# 467444_130_3_1-R0.net
KiCad netlist of a schematic drawn in Altium Designer
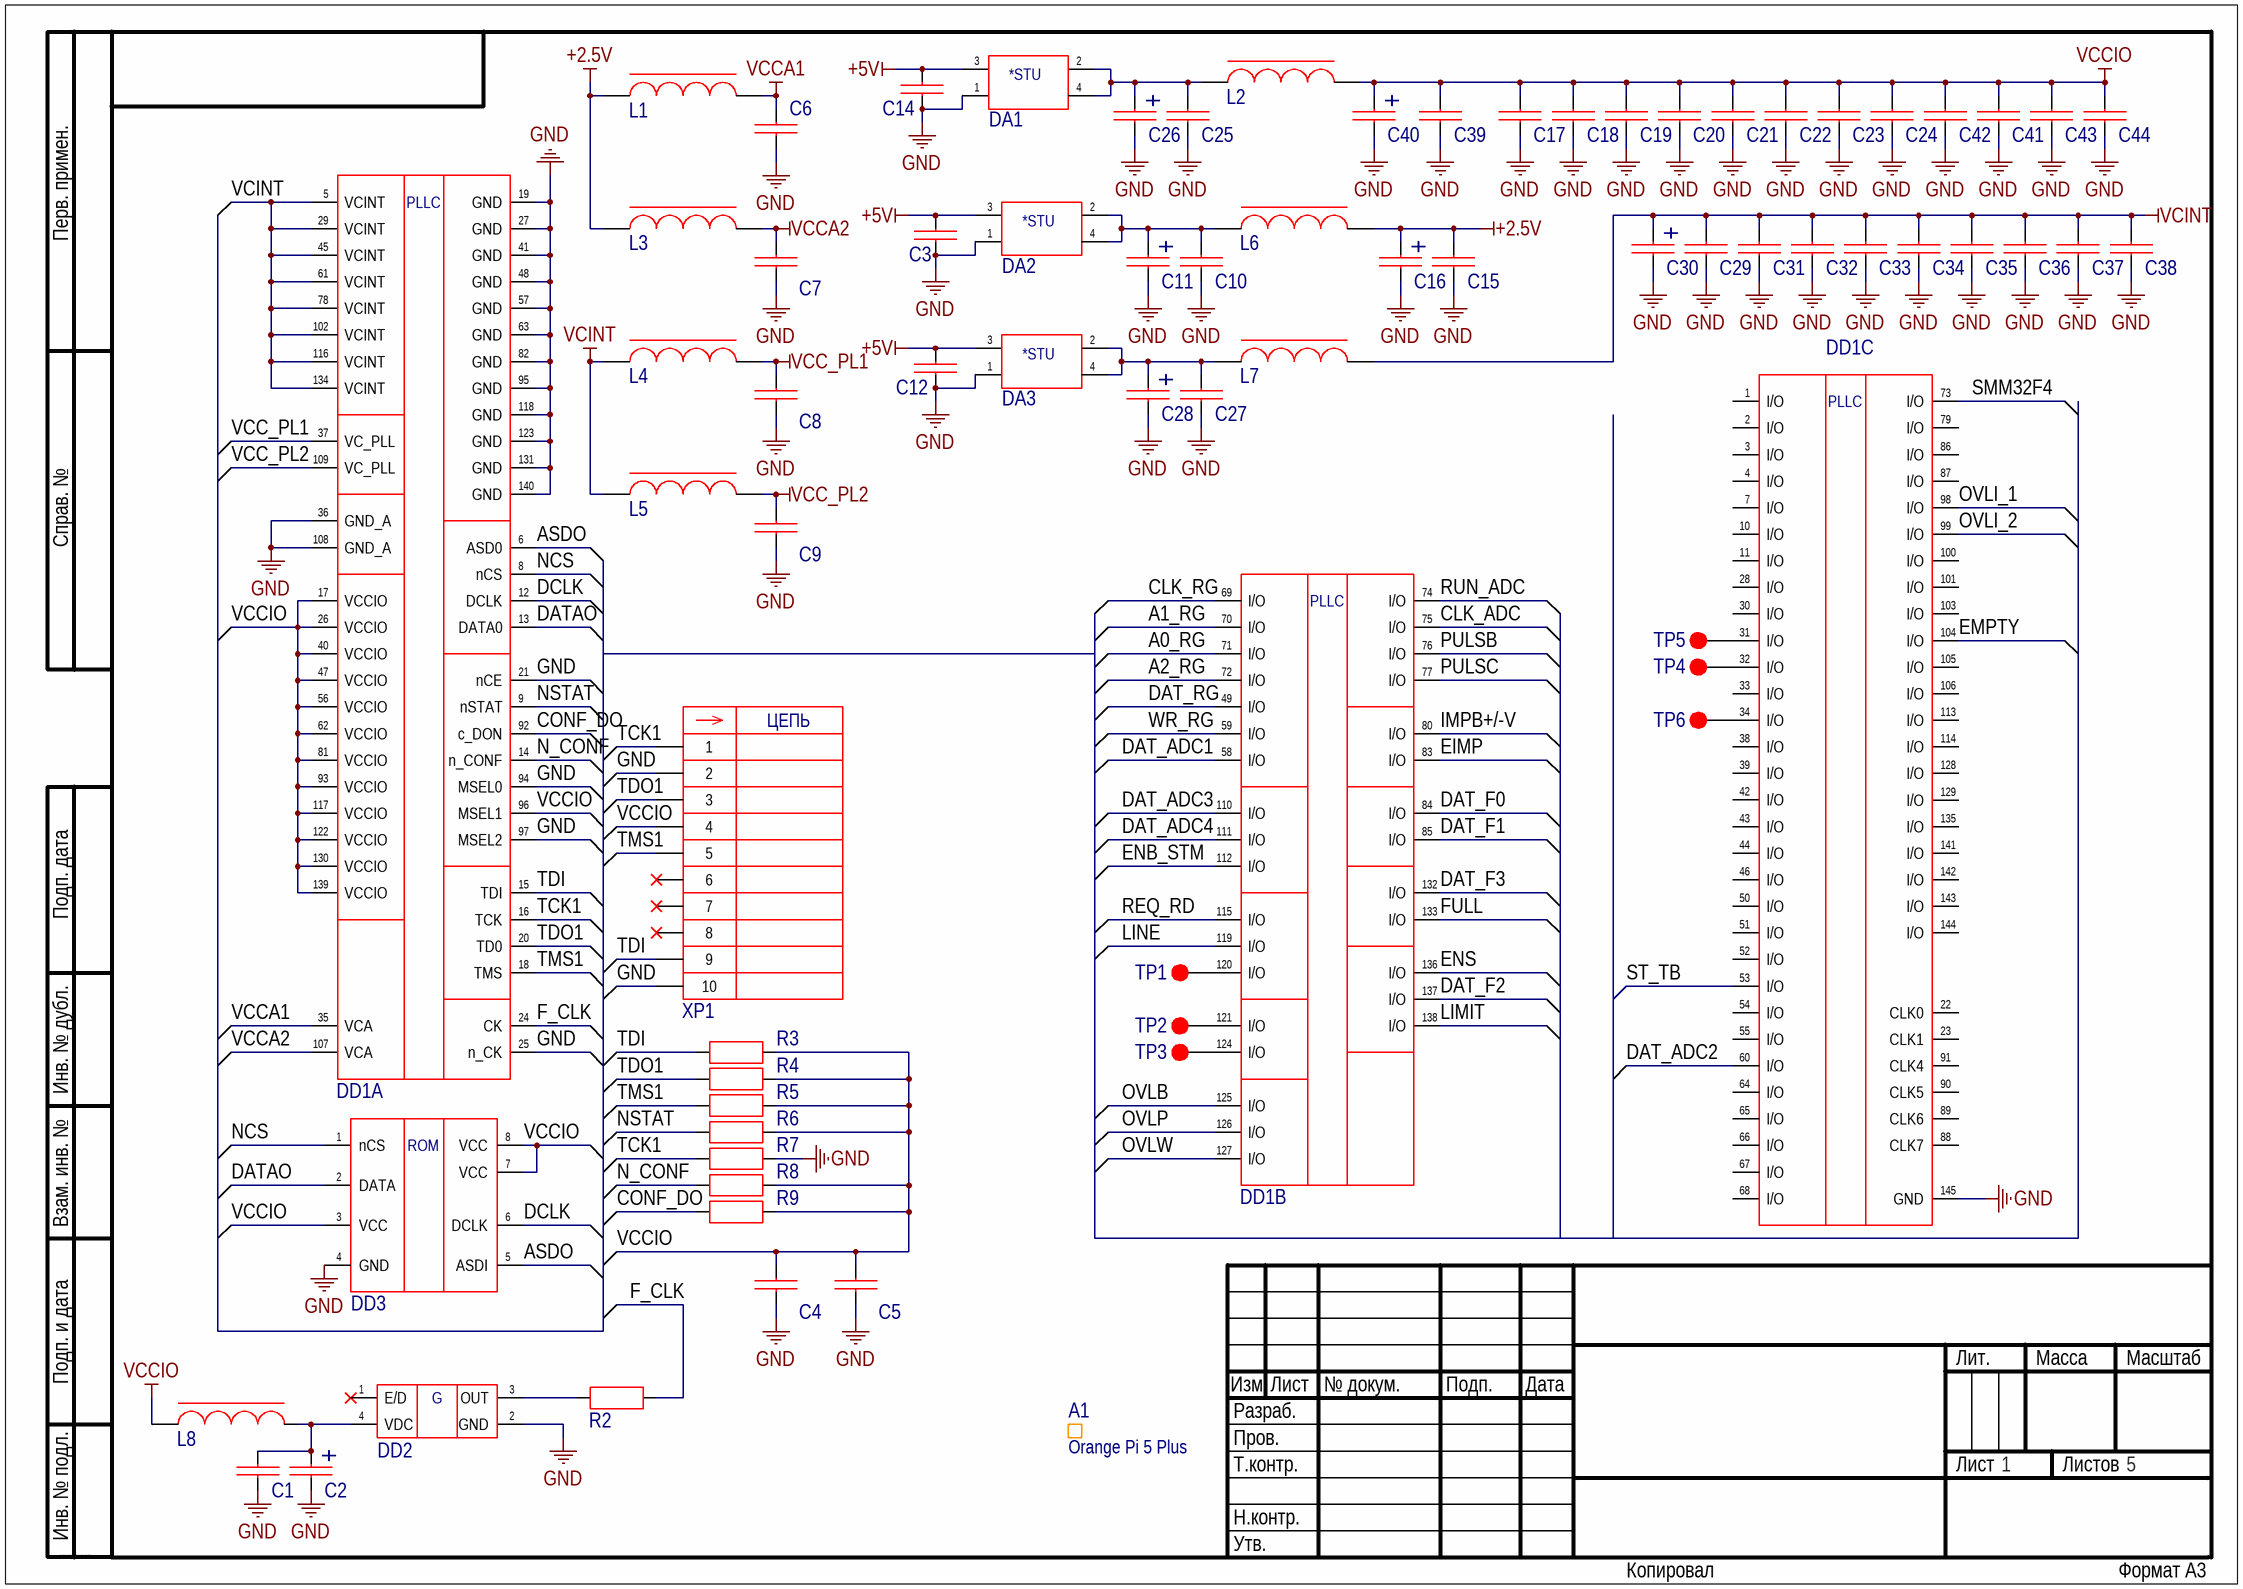
[diagram p0: УШЯИ.467444.130Э3_1-R0.SchDoc]

(export (version "E")
  (design (tool "Eeschema 10.0.6"))
  (components
    (comp (ref "A1")
      (value "Orange Pi 5 Plus")
      (footprint "Orange_Pi_5_Plus")
      (description "8GB Rockchip RK3588, HDMI 2.1, Gigabit LAN port, USB2.0/3.0, microSD card slot, USB Type-C")
      (fields (field (name "MANUFACTURER") "Orange Pi"))
      (libsource (lib "lib") (part "0"))
    )
    (comp (ref "C1")
      (value "0,1 µF")
      (footprint "C_0805 [2012 Metric]")
      (description "Неполярный конденсатор")
      (fields (field (name "MANUFACTURER") "Murata") (field (name "VOLTAGE") "50V"))
      (libsource (lib "lib") (part "C_const"))
    )
    (comp (ref "C2")
      (value "4,7 µF")
      (footprint "C+_1210 [3528-21 Metric]")
      (description "Полярный конденсатор")
      (fields (field (name "MANUFACTURER") "KYOCERA AVX") (field (name "VOLTAGE") "20V\r\n10V"))
      (libsource (lib "lib") (part "C_electrolytic"))
    )
    (comp (ref "C3")
      (value "0,1 µF")
      (footprint "C_0805 [2012 Metric]")
      (description "Неполярный конденсатор")
      (fields (field (name "MANUFACTURER") "Murata") (field (name "VOLTAGE") "25V"))
      (libsource (lib "lib") (part "C_const"))
    )
    (comp (ref "C4")
      (value "1 µF")
      (footprint "C_0805 [2012 Metric]")
      (description "Неполярный конденсатор")
      (fields (field (name "MANUFACTURER") "Murata") (field (name "VOLTAGE") "16V"))
      (libsource (lib "lib") (part "C_const"))
    )
    (comp (ref "C5")
      (value "1 µF")
      (footprint "C_0805 [2012 Metric]")
      (description "Неполярный конденсатор")
      (fields (field (name "MANUFACTURER") "Murata") (field (name "VOLTAGE") "16V"))
      (libsource (lib "lib") (part "C_const"))
    )
    (comp (ref "C6")
      (value "0,1 µF")
      (footprint "C_0805 [2012 Metric]")
      (description "Неполярный конденсатор")
      (fields (field (name "MANUFACTURER") "Murata") (field (name "VOLTAGE") "25V"))
      (libsource (lib "lib") (part "C_const"))
    )
    (comp (ref "C7")
      (value "0,1 µF")
      (footprint "C_0805 [2012 Metric]")
      (description "Неполярный конденсатор")
      (fields (field (name "MANUFACTURER") "Murata") (field (name "VOLTAGE") "25V"))
      (libsource (lib "lib") (part "C_const"))
    )
    (comp (ref "C8")
      (value "0,1 µF")
      (footprint "C_0805 [2012 Metric]")
      (description "Неполярный конденсатор")
      (fields (field (name "MANUFACTURER") "Murata") (field (name "VOLTAGE") "25V"))
      (libsource (lib "lib") (part "C_const"))
    )
    (comp (ref "C9")
      (value "0,1 µF")
      (footprint "C_0805 [2012 Metric]")
      (description "Неполярный конденсатор")
      (fields (field (name "MANUFACTURER") "Murata") (field (name "VOLTAGE") "25V"))
      (libsource (lib "lib") (part "C_const"))
    )
    (comp (ref "C10")
      (value "0,1 µF")
      (footprint "C_0805 [2012 Metric]")
      (description "Неполярный конденсатор")
      (fields (field (name "MANUFACTURER") "Murata") (field (name "VOLTAGE") "25V"))
      (libsource (lib "lib") (part "C_const"))
    )
    (comp (ref "C11")
      (value "4,7 µF")
      (footprint "C+_1210 [3528-21 Metric]")
      (description "Полярный конденсатор")
      (fields (field (name "MANUFACTURER") "KYOCERA AVX") (field (name "VOLTAGE") "20V\r\n10V"))
      (libsource (lib "lib") (part "C_electrolytic"))
    )
    (comp (ref "C12")
      (value "0,1 µF")
      (footprint "C_0805 [2012 Metric]")
      (description "Неполярный конденсатор")
      (fields (field (name "MANUFACTURER") "Murata") (field (name "VOLTAGE") "25V"))
      (libsource (lib "lib") (part "C_const"))
    )
    (comp (ref "C14")
      (value "0,1 µF")
      (footprint "C_0805 [2012 Metric]")
      (description "Неполярный конденсатор")
      (fields (field (name "MANUFACTURER") "Murata") (field (name "VOLTAGE") "25V"))
      (libsource (lib "lib") (part "C_const"))
    )
    (comp (ref "C15")
      (value "0,1 µF")
      (footprint "C_0805 [2012 Metric]")
      (description "Неполярный конденсатор")
      (fields (field (name "MANUFACTURER") "Murata") (field (name "VOLTAGE") "25V"))
      (libsource (lib "lib") (part "C_const"))
    )
    (comp (ref "C16")
      (value "10 µF")
      (footprint "C+_1210 [3528-21 Metric]")
      (description "Полярный конденсатор")
      (fields (field (name "MANUFACTURER") "KYOCERA AVX") (field (name "VOLTAGE") "20V\r\n10V"))
      (libsource (lib "lib") (part "C_electrolytic"))
    )
    (comp (ref "C17")
      (value "0,1 µF")
      (footprint "C_0805 [2012 Metric]")
      (description "Неполярный конденсатор")
      (fields (field (name "MANUFACTURER") "Murata") (field (name "VOLTAGE") "25V"))
      (libsource (lib "lib") (part "C_const"))
    )
    (comp (ref "C18")
      (value "0,1 µF")
      (footprint "C_0805 [2012 Metric]")
      (description "Неполярный конденсатор")
      (fields (field (name "MANUFACTURER") "Murata") (field (name "VOLTAGE") "25V"))
      (libsource (lib "lib") (part "C_const"))
    )
    (comp (ref "C19")
      (value "0,1 µF")
      (footprint "C_0805 [2012 Metric]")
      (description "Неполярный конденсатор")
      (fields (field (name "MANUFACTURER") "Murata") (field (name "VOLTAGE") "25V"))
      (libsource (lib "lib") (part "C_const"))
    )
    (comp (ref "C20")
      (value "0,1 µF")
      (footprint "C_0805 [2012 Metric]")
      (description "Неполярный конденсатор")
      (fields (field (name "MANUFACTURER") "Murata") (field (name "VOLTAGE") "25V"))
      (libsource (lib "lib") (part "C_const"))
    )
    (comp (ref "C21")
      (value "0,1 µF")
      (footprint "C_0805 [2012 Metric]")
      (description "Неполярный конденсатор")
      (fields (field (name "MANUFACTURER") "Murata") (field (name "VOLTAGE") "25V"))
      (libsource (lib "lib") (part "C_const"))
    )
    (comp (ref "C22")
      (value "0,1 µF")
      (footprint "C_0805 [2012 Metric]")
      (description "Неполярный конденсатор")
      (fields (field (name "MANUFACTURER") "Murata") (field (name "VOLTAGE") "25V"))
      (libsource (lib "lib") (part "C_const"))
    )
    (comp (ref "C23")
      (value "0,1 µF")
      (footprint "C_0805 [2012 Metric]")
      (description "Неполярный конденсатор")
      (fields (field (name "MANUFACTURER") "Murata") (field (name "VOLTAGE") "25V"))
      (libsource (lib "lib") (part "C_const"))
    )
    (comp (ref "C24")
      (value "0,1 µF")
      (footprint "C_0805 [2012 Metric]")
      (description "Неполярный конденсатор")
      (fields (field (name "MANUFACTURER") "Murata") (field (name "VOLTAGE") "25V"))
      (libsource (lib "lib") (part "C_const"))
    )
    (comp (ref "C25")
      (value "0,1 µF")
      (footprint "C_0805 [2012 Metric]")
      (description "Неполярный конденсатор")
      (fields (field (name "MANUFACTURER") "Murata") (field (name "VOLTAGE") "25V"))
      (libsource (lib "lib") (part "C_const"))
    )
    (comp (ref "C26")
      (value "4,7 µF")
      (footprint "C+_1210 [3528-21 Metric]")
      (description "Полярный конденсатор")
      (fields (field (name "MANUFACTURER") "KYOCERA AVX") (field (name "VOLTAGE") "20V\r\n10V"))
      (libsource (lib "lib") (part "C_electrolytic"))
    )
    (comp (ref "C27")
      (value "0,1 µF")
      (footprint "C_0805 [2012 Metric]")
      (description "Неполярный конденсатор")
      (fields (field (name "MANUFACTURER") "Murata") (field (name "VOLTAGE") "50V"))
      (libsource (lib "lib") (part "C_const"))
    )
    (comp (ref "C28")
      (value "4,7 µF")
      (footprint "C+_1210 [3528-21 Metric]")
      (description "Полярный конденсатор")
      (fields (field (name "MANUFACTURER") "KYOCERA AVX") (field (name "VOLTAGE") "20V\r\n10V"))
      (libsource (lib "lib") (part "C_electrolytic"))
    )
    (comp (ref "C29")
      (value "0,1 µF")
      (footprint "C_0805 [2012 Metric]")
      (description "Неполярный конденсатор")
      (fields (field (name "MANUFACTURER") "Murata") (field (name "VOLTAGE") "50V"))
      (libsource (lib "lib") (part "C_const"))
    )
    (comp (ref "C30")
      (value "4,7 µF")
      (footprint "C+_1210 [3528-21 Metric]")
      (description "Полярный конденсатор")
      (fields (field (name "MANUFACTURER") "KYOCERA AVX") (field (name "VOLTAGE") "20V\r\n10V"))
      (libsource (lib "lib") (part "C_electrolytic"))
    )
    (comp (ref "C31")
      (value "0,1 µF")
      (footprint "C_0805 [2012 Metric]")
      (description "Неполярный конденсатор")
      (fields (field (name "MANUFACTURER") "Murata") (field (name "VOLTAGE") "50V"))
      (libsource (lib "lib") (part "C_const"))
    )
    (comp (ref "C32")
      (value "0,1 µF")
      (footprint "C_0805 [2012 Metric]")
      (description "Неполярный конденсатор")
      (fields (field (name "MANUFACTURER") "Murata") (field (name "VOLTAGE") "50V"))
      (libsource (lib "lib") (part "C_const"))
    )
    (comp (ref "C33")
      (value "0,1 µF")
      (footprint "C_0805 [2012 Metric]")
      (description "Неполярный конденсатор")
      (fields (field (name "MANUFACTURER") "Murata") (field (name "VOLTAGE") "50V"))
      (libsource (lib "lib") (part "C_const"))
    )
    (comp (ref "C34")
      (value "0,1 µF")
      (footprint "C_0805 [2012 Metric]")
      (description "Неполярный конденсатор")
      (fields (field (name "MANUFACTURER") "Murata") (field (name "VOLTAGE") "50V"))
      (libsource (lib "lib") (part "C_const"))
    )
    (comp (ref "C35")
      (value "0,1 µF")
      (footprint "C_0805 [2012 Metric]")
      (description "Неполярный конденсатор")
      (fields (field (name "MANUFACTURER") "Murata") (field (name "VOLTAGE") "50V"))
      (libsource (lib "lib") (part "C_const"))
    )
    (comp (ref "C36")
      (value "0,1 µF")
      (footprint "C_0805 [2012 Metric]")
      (description "Неполярный конденсатор")
      (fields (field (name "MANUFACTURER") "Murata") (field (name "VOLTAGE") "50V"))
      (libsource (lib "lib") (part "C_const"))
    )
    (comp (ref "C37")
      (value "0,1 µF")
      (footprint "C_0805 [2012 Metric]")
      (description "Неполярный конденсатор")
      (fields (field (name "MANUFACTURER") "Murata") (field (name "VOLTAGE") "50V"))
      (libsource (lib "lib") (part "C_const"))
    )
    (comp (ref "C38")
      (value "0,1 µF")
      (footprint "C_0805 [2012 Metric]")
      (description "Неполярный конденсатор")
      (fields (field (name "MANUFACTURER") "Murata") (field (name "VOLTAGE") "50V"))
      (libsource (lib "lib") (part "C_const"))
    )
    (comp (ref "C39")
      (value "0,1 µF")
      (footprint "C_0805 [2012 Metric]")
      (description "Неполярный конденсатор")
      (fields (field (name "MANUFACTURER") "Murata") (field (name "VOLTAGE") "50V"))
      (libsource (lib "lib") (part "C_const"))
    )
    (comp (ref "C40")
      (value "10 µF")
      (footprint "C+_1210 [3528-21 Metric]")
      (description "Полярный конденсатор")
      (fields (field (name "MANUFACTURER") "KYOCERA AVX") (field (name "VOLTAGE") "20V\r\n10V"))
      (libsource (lib "lib") (part "C_electrolytic"))
    )
    (comp (ref "C41")
      (value "0,1 µF")
      (footprint "C_0805 [2012 Metric]")
      (description "Неполярный конденсатор")
      (fields (field (name "MANUFACTURER") "Murata") (field (name "VOLTAGE") "50V"))
      (libsource (lib "lib") (part "C_const"))
    )
    (comp (ref "C42")
      (value "0,1 µF")
      (footprint "C_0805 [2012 Metric]")
      (description "Неполярный конденсатор")
      (fields (field (name "MANUFACTURER") "Murata") (field (name "VOLTAGE") "50V"))
      (libsource (lib "lib") (part "C_const"))
    )
    (comp (ref "C43")
      (value "0,1 µF")
      (footprint "C_0805 [2012 Metric]")
      (description "Неполярный конденсатор")
      (fields (field (name "MANUFACTURER") "Murata") (field (name "VOLTAGE") "50V"))
      (libsource (lib "lib") (part "C_const"))
    )
    (comp (ref "C44")
      (value "0,1 µF")
      (footprint "C_0805 [2012 Metric]")
      (description "Неполярный конденсатор")
      (fields (field (name "MANUFACTURER") "Murata") (field (name "VOLTAGE") "50V"))
      (libsource (lib "lib") (part "C_const"))
    )
    (comp (ref "DA1")
      (value "LD1117AS33TR")
      (footprint "SOT-223")
      (description "IC, Fixed LDO Voltage Regulator, 5.3V to 10V, 1.15V Dropout, 3.3Vout, 1Aout")
      (fields (field (name "MANUFACTURER") "STMicroelectronics"))
      (libsource (lib "lib") (part "VolReg_LD1117AS33TR"))
    )
    (comp (ref "DA2")
      (value "LD1117AS25TR")
      (footprint "SOT-223")
      (description "IC, Linear Voltage Regulator, 1 Output, 1V Dropout, 2.5Vout, 1Aout")
      (fields (field (name "MANUFACTURER") "STMicroelectronics"))
      (libsource (lib "lib") (part "VolReg_LD1117AS33TR"))
    )
    (comp (ref "DA3")
      (value "LD1117AS12TR")
      (footprint "SOT-223")
      (description "IC, Fixed LDO Voltage Regulator, 1 Output, 1V Dropout, 1.2Vout, 1Aout")
      (fields (field (name "MANUFACTURER") "STMicroelectronics"))
      (libsource (lib "lib") (part "VolReg_LD1117AS33TR"))
    )
    (comp (ref "DD1")
      (value "EP3C5E144I7")
      (footprint "EQFP-144[20x20]_0.5_22x22x1.6")
      (description "IC, Cyclone III, Field Programmable Gate Array (FPGA), 	1.15V to 1.25V, 315 MHz, 94 I/O")
      (fields (field (name "MANUFACTURER") "Intel"))
      (libsource (lib "lib") (part "EP3C5E144I7"))
    )
    (comp (ref "DD2")
      (value "O 20,0-JO32-B-3.3-1-T1-LF")
      (footprint "JO32")
      (description "Crystals, Oscillators, 20 MHz")
      (fields (field (name "MANUFACTURER") "Jauch Quartz GmbH"))
      (libsource (lib "lib") (part "JO32"))
    )
    (comp (ref "DD3")
      (value "EPCS4SI8N")
      (footprint "SOIC-8_1.27_5x4x1.75")
      (description "IC, FPGA Configuration Memory, Flash, 4 Mbit, 40 MHz, JTAG, Serial")
      (fields (field (name "MANUFACTURER") "Intel"))
      (libsource (lib "lib") (part "EPCS4"))
    )
    (comp (ref "L1")
      (value "0,22 μH")
      (footprint "IND_LQH31CN")
      (fields (field (name "MANUFACTURER") "Murata") (field (name "TOLERANCE") "±20%"))
      (libsource (lib "lib") (part "IND_ferromagnetic/ferrite_core"))
    )
    (comp (ref "L2")
      (value "~")
      (footprint "IND_0805 [2012 Metric]")
      (fields (field (name "MANUFACTURER") "Vishay") (field (name "TOLERANCE") "±25%"))
      (libsource (lib "lib") (part "IND_ferromagnetic/ferrite_core"))
    )
    (comp (ref "L3")
      (value "0,22 μH")
      (footprint "IND_LQH31CN")
      (fields (field (name "MANUFACTURER") "Murata") (field (name "TOLERANCE") "±20%"))
      (libsource (lib "lib") (part "IND_ferromagnetic/ferrite_core"))
    )
    (comp (ref "L4")
      (value "0,22 μH")
      (footprint "IND_LQH31CN")
      (fields (field (name "MANUFACTURER") "Murata") (field (name "TOLERANCE") "±20%"))
      (libsource (lib "lib") (part "IND_ferromagnetic/ferrite_core"))
    )
    (comp (ref "L5")
      (value "0,22 μH")
      (footprint "IND_LQH31CN")
      (fields (field (name "MANUFACTURER") "Murata") (field (name "TOLERANCE") "±20%"))
      (libsource (lib "lib") (part "IND_ferromagnetic/ferrite_core"))
    )
    (comp (ref "L6")
      (value "~")
      (footprint "IND_0805 [2012 Metric]")
      (fields (field (name "MANUFACTURER") "Vishay") (field (name "TOLERANCE") "±25%"))
      (libsource (lib "lib") (part "IND_ferromagnetic/ferrite_core"))
    )
    (comp (ref "L7")
      (value "~")
      (footprint "IND_0805 [2012 Metric]")
      (fields (field (name "MANUFACTURER") "Vishay") (field (name "TOLERANCE") "±25%"))
      (libsource (lib "lib") (part "IND_ferromagnetic/ferrite_core"))
    )
    (comp (ref "L8")
      (value "~")
      (footprint "IND_0805 [2012 Metric]")
      (fields (field (name "MANUFACTURER") "Vishay") (field (name "TOLERANCE") "±25%"))
      (libsource (lib "lib") (part "IND_ferromagnetic/ferrite_core"))
    )
    (comp (ref "R2")
      (value "51R")
      (footprint "R_0805 [2012 Metric]")
      (fields (field (name "TOLERANCE") "±5%"))
      (libsource (lib "lib") (part "R_Const"))
    )
    (comp (ref "R3")
      (value "1k")
      (footprint "R_0805 [2012 Metric]")
      (fields (field (name "TOLERANCE") "±5%"))
      (libsource (lib "lib") (part "R_Const"))
    )
    (comp (ref "R4")
      (value "10k")
      (footprint "R_0805 [2012 Metric]")
      (fields (field (name "TOLERANCE") "±5%"))
      (libsource (lib "lib") (part "R_Const"))
    )
    (comp (ref "R5")
      (value "1k")
      (footprint "R_0805 [2012 Metric]")
      (fields (field (name "TOLERANCE") "±5%"))
      (libsource (lib "lib") (part "R_Const"))
    )
    (comp (ref "R6")
      (value "10k")
      (footprint "R_0805 [2012 Metric]")
      (fields (field (name "TOLERANCE") "±5%"))
      (libsource (lib "lib") (part "R_Const"))
    )
    (comp (ref "R7")
      (value "1k")
      (footprint "R_0805 [2012 Metric]")
      (fields (field (name "TOLERANCE") "±5%"))
      (libsource (lib "lib") (part "R_Const"))
    )
    (comp (ref "R8")
      (value "10k")
      (footprint "R_0805 [2012 Metric]")
      (fields (field (name "TOLERANCE") "±5%"))
      (libsource (lib "lib") (part "R_Const"))
    )
    (comp (ref "R9")
      (value "10k")
      (footprint "R_0805 [2012 Metric]")
      (fields (field (name "TOLERANCE") "±5%"))
      (libsource (lib "lib") (part "R_Const"))
    )
    (comp (ref "TP1") (value "~") (footprint "DSP_1.3") (libsource (lib "lib") (part "TP")))
    (comp (ref "TP2") (value "~") (footprint "DSP_1.3") (libsource (lib "lib") (part "TP")))
    (comp (ref "TP3") (value "~") (footprint "DSP_1.3") (libsource (lib "lib") (part "TP")))
    (comp (ref "TP4") (value "~") (footprint "DSP_1.3") (libsource (lib "lib") (part "TP")))
    (comp (ref "TP5") (value "~") (footprint "DSP_1.3") (libsource (lib "lib") (part "TP")))
    (comp (ref "TP6") (value "~") (footprint "DSP_1.3") (libsource (lib "lib") (part "TP")))
    (comp (ref "XP1")
      (value "PLD-10")
      (footprint "PLD-10")
      (description "Male, 10 pins, 2 rows, Vertical")
      (fields (field (name "MANUFACTURER") "Connfly electronic"))
      (libsource (lib "lib") (part "M_10"))
    )
  )
  (nets
    (net (code "1") (name "+2.5V") (class "Default")
      (node (ref "C15") (pin "2") (pinfunction "2_2") (pintype "passive"))
      (node (ref "C16") (pin "+") (pinfunction "+_+") (pintype "passive"))
      (node (ref "L1") (pin "1") (pinfunction "1_1") (pintype "passive"))
      (node (ref "L3") (pin "1") (pinfunction "1_1") (pintype "passive"))
      (node (ref "L6") (pin "2") (pinfunction "2_2") (pintype "passive"))
    )
    (net (code "2") (name "+5V") (class "Default")
      (node (ref "C12") (pin "2") (pinfunction "2_2") (pintype "passive"))
      (node (ref "C14") (pin "2") (pinfunction "2_2") (pintype "passive"))
      (node (ref "C3") (pin "2") (pinfunction "2_2") (pintype "passive"))
      (node (ref "DA1") (pin "3") (pinfunction "VIN_3") (pintype "passive"))
      (node (ref "DA2") (pin "3") (pinfunction "VIN_3") (pintype "passive"))
      (node (ref "DA3") (pin "3") (pinfunction "VIN_3") (pintype "passive"))
    )
    (net (code "3") (name "/A0_RG") (class "Default")
      (node (ref "DD1") (pin "71") (pinfunction "I/O_71") (pintype "passive"))
    )
    (net (code "4") (name "/A1_RG") (class "Default")
      (node (ref "DD1") (pin "70") (pinfunction "I/O_70") (pintype "passive"))
    )
    (net (code "5") (name "/A2_RG") (class "Default")
      (node (ref "DD1") (pin "72") (pinfunction "I/O_72") (pintype "passive"))
    )
    (net (code "6") (name "/ASDO") (class "Default")
      (node (ref "DD1") (pin "6") (pinfunction "ASD0_6") (pintype "passive"))
      (node (ref "DD3") (pin "5") (pinfunction "ASDI_5") (pintype "passive"))
    )
    (net (code "7") (name "/CLK_ADC") (class "Default")
      (node (ref "DD1") (pin "75") (pinfunction "I/O_75") (pintype "passive"))
    )
    (net (code "8") (name "/CLK_RG") (class "Default")
      (node (ref "DD1") (pin "69") (pinfunction "I/O_69") (pintype "passive"))
    )
    (net (code "9") (name "/CONF_DO") (class "Default")
      (node (ref "DD1") (pin "92") (pinfunction "c_DON_92") (pintype "passive"))
      (node (ref "R9") (pin "1") (pinfunction "1_1") (pintype "passive"))
    )
    (net (code "10") (name "/DATAO") (class "Default")
      (node (ref "DD1") (pin "13") (pinfunction "DATA0_13") (pintype "passive"))
      (node (ref "DD3") (pin "2") (pinfunction "DATA_2") (pintype "passive"))
    )
    (net (code "11") (name "/DAT_ADC1") (class "Default")
      (node (ref "DD1") (pin "58") (pinfunction "I/O_58") (pintype "passive"))
    )
    (net (code "12") (name "/DAT_ADC2") (class "Default")
      (node (ref "DD1") (pin "60") (pinfunction "I/O_60") (pintype "passive"))
    )
    (net (code "13") (name "/DAT_ADC3") (class "Default")
      (node (ref "DD1") (pin "110") (pinfunction "I/O_110") (pintype "passive"))
    )
    (net (code "14") (name "/DAT_ADC4") (class "Default")
      (node (ref "DD1") (pin "111") (pinfunction "I/O_111") (pintype "passive"))
    )
    (net (code "15") (name "/DAT_F0") (class "Default")
      (node (ref "DD1") (pin "84") (pinfunction "I/O_84") (pintype "passive"))
    )
    (net (code "16") (name "/DAT_F1") (class "Default")
      (node (ref "DD1") (pin "85") (pinfunction "I/O_85") (pintype "passive"))
    )
    (net (code "17") (name "/DAT_F2") (class "Default")
      (node (ref "DD1") (pin "137") (pinfunction "I/O_137") (pintype "passive"))
    )
    (net (code "18") (name "/DAT_F3") (class "Default")
      (node (ref "DD1") (pin "132") (pinfunction "I/O_132") (pintype "passive"))
    )
    (net (code "19") (name "/DAT_RG") (class "Default")
      (node (ref "DD1") (pin "49") (pinfunction "I/O_49") (pintype "passive"))
    )
    (net (code "20") (name "/DCLK") (class "Default")
      (node (ref "DD1") (pin "12") (pinfunction "DCLK_12") (pintype "passive"))
      (node (ref "DD3") (pin "6") (pinfunction "DCLK_6") (pintype "passive"))
    )
    (net (code "21") (name "/EIMP") (class "Default")
      (node (ref "DD1") (pin "83") (pinfunction "I/O_83") (pintype "passive"))
    )
    (net (code "22") (name "/EMPTY") (class "Default")
      (node (ref "DD1") (pin "104") (pinfunction "I/O_104") (pintype "passive"))
    )
    (net (code "23") (name "/ENB_STM") (class "Default")
      (node (ref "DD1") (pin "112") (pinfunction "I/O_112") (pintype "passive"))
    )
    (net (code "24") (name "/ENS") (class "Default")
      (node (ref "DD1") (pin "136") (pinfunction "I/O_136") (pintype "passive"))
    )
    (net (code "25") (name "/FULL") (class "Default")
      (node (ref "DD1") (pin "133") (pinfunction "I/O_133") (pintype "passive"))
    )
    (net (code "26") (name "/F_CLK") (class "Default")
      (node (ref "DD1") (pin "24") (pinfunction "CK_24") (pintype "passive"))
      (node (ref "R2") (pin "2") (pinfunction "2_2") (pintype "passive"))
    )
    (net (code "27") (name "/IMPB+{slash}-V") (class "Default")
      (node (ref "DD1") (pin "80") (pinfunction "I/O_80") (pintype "passive"))
    )
    (net (code "28") (name "/LIMIT") (class "Default")
      (node (ref "DD1") (pin "138") (pinfunction "I/O_138") (pintype "passive"))
    )
    (net (code "29") (name "/LINE") (class "Default")
      (node (ref "DD1") (pin "119") (pinfunction "I/O_119") (pintype "passive"))
    )
    (net (code "30") (name "/NCS") (class "Default")
      (node (ref "DD1") (pin "8") (pinfunction "nCS_8") (pintype "passive"))
      (node (ref "DD3") (pin "1") (pinfunction "nCS_1") (pintype "passive"))
    )
    (net (code "31") (name "/NSTAT") (class "Default")
      (node (ref "DD1") (pin "9") (pinfunction "nSTAT_9") (pintype "passive"))
      (node (ref "R6") (pin "1") (pinfunction "1_1") (pintype "passive"))
    )
    (net (code "32") (name "/N_CONF") (class "Default")
      (node (ref "DD1") (pin "14") (pinfunction "n_CONF_14") (pintype "passive"))
      (node (ref "R8") (pin "1") (pinfunction "1_1") (pintype "passive"))
    )
    (net (code "33") (name "/OVLB") (class "Default")
      (node (ref "DD1") (pin "125") (pinfunction "I/O_125") (pintype "passive"))
    )
    (net (code "34") (name "/OVLI_1") (class "Default")
      (node (ref "DD1") (pin "98") (pinfunction "I/O_98") (pintype "passive"))
    )
    (net (code "35") (name "/OVLI_2") (class "Default")
      (node (ref "DD1") (pin "99") (pinfunction "I/O_99") (pintype "passive"))
    )
    (net (code "36") (name "/OVLP") (class "Default")
      (node (ref "DD1") (pin "126") (pinfunction "I/O_126") (pintype "passive"))
    )
    (net (code "37") (name "/OVLW") (class "Default")
      (node (ref "DD1") (pin "127") (pinfunction "I/O_127") (pintype "passive"))
    )
    (net (code "38") (name "/PULSB") (class "Default")
      (node (ref "DD1") (pin "76") (pinfunction "I/O_76") (pintype "passive"))
    )
    (net (code "39") (name "/PULSC") (class "Default")
      (node (ref "DD1") (pin "77") (pinfunction "I/O_77") (pintype "passive"))
    )
    (net (code "40") (name "/REQ_RD") (class "Default")
      (node (ref "DD1") (pin "115") (pinfunction "I/O_115") (pintype "passive"))
    )
    (net (code "41") (name "/RUN_ADC") (class "Default")
      (node (ref "DD1") (pin "74") (pinfunction "I/O_74") (pintype "passive"))
    )
    (net (code "42") (name "/SMM32F4") (class "Default")
      (node (ref "DD1") (pin "73") (pinfunction "I/O_73") (pintype "passive"))
    )
    (net (code "43") (name "/ST_TB") (class "Default")
      (node (ref "DD1") (pin "53") (pinfunction "I/O_53") (pintype "passive"))
    )
    (net (code "44") (name "/TCK1") (class "Default")
      (node (ref "DD1") (pin "16") (pinfunction "TCK_16") (pintype "passive"))
      (node (ref "R7") (pin "1") (pinfunction "1_1") (pintype "passive"))
      (node (ref "XP1") (pin "1") (pinfunction "1_1") (pintype "passive"))
    )
    (net (code "45") (name "/TDI") (class "Default")
      (node (ref "DD1") (pin "15") (pinfunction "TDI_15") (pintype "passive"))
      (node (ref "R3") (pin "1") (pinfunction "1_1") (pintype "passive"))
      (node (ref "XP1") (pin "9") (pinfunction "9_9") (pintype "passive"))
    )
    (net (code "46") (name "/TDO1") (class "Default")
      (node (ref "DD1") (pin "20") (pinfunction "TD0_20") (pintype "passive"))
      (node (ref "R4") (pin "1") (pinfunction "1_1") (pintype "passive"))
      (node (ref "XP1") (pin "3") (pinfunction "3_3") (pintype "passive"))
    )
    (net (code "47") (name "/TMS1") (class "Default")
      (node (ref "DD1") (pin "18") (pinfunction "TMS_18") (pintype "passive"))
      (node (ref "R5") (pin "1") (pinfunction "1_1") (pintype "passive"))
      (node (ref "XP1") (pin "5") (pinfunction "5_5") (pintype "passive"))
    )
    (net (code "48") (name "/WR_RG") (class "Default")
      (node (ref "DD1") (pin "59") (pinfunction "I/O_59") (pintype "passive"))
    )
    (net (code "49") (name "GND") (class "Default")
      (node (ref "C1") (pin "1") (pinfunction "1_1") (pintype "passive"))
      (node (ref "C10") (pin "1") (pinfunction "1_1") (pintype "passive"))
      (node (ref "C11") (pin "-") (pinfunction "-_-") (pintype "passive"))
      (node (ref "C12") (pin "1") (pinfunction "1_1") (pintype "passive"))
      (node (ref "C14") (pin "1") (pinfunction "1_1") (pintype "passive"))
      (node (ref "C15") (pin "1") (pinfunction "1_1") (pintype "passive"))
      (node (ref "C16") (pin "-") (pinfunction "-_-") (pintype "passive"))
      (node (ref "C17") (pin "1") (pinfunction "1_1") (pintype "passive"))
      (node (ref "C18") (pin "1") (pinfunction "1_1") (pintype "passive"))
      (node (ref "C19") (pin "1") (pinfunction "1_1") (pintype "passive"))
      (node (ref "C2") (pin "-") (pinfunction "-_-") (pintype "passive"))
      (node (ref "C20") (pin "1") (pinfunction "1_1") (pintype "passive"))
      (node (ref "C21") (pin "1") (pinfunction "1_1") (pintype "passive"))
      (node (ref "C22") (pin "1") (pinfunction "1_1") (pintype "passive"))
      (node (ref "C23") (pin "1") (pinfunction "1_1") (pintype "passive"))
      (node (ref "C24") (pin "1") (pinfunction "1_1") (pintype "passive"))
      (node (ref "C25") (pin "1") (pinfunction "1_1") (pintype "passive"))
      (node (ref "C26") (pin "-") (pinfunction "-_-") (pintype "passive"))
      (node (ref "C27") (pin "1") (pinfunction "1_1") (pintype "passive"))
      (node (ref "C28") (pin "-") (pinfunction "-_-") (pintype "passive"))
      (node (ref "C29") (pin "1") (pinfunction "1_1") (pintype "passive"))
      (node (ref "C3") (pin "1") (pinfunction "1_1") (pintype "passive"))
      (node (ref "C30") (pin "-") (pinfunction "-_-") (pintype "passive"))
      (node (ref "C31") (pin "1") (pinfunction "1_1") (pintype "passive"))
      (node (ref "C32") (pin "1") (pinfunction "1_1") (pintype "passive"))
      (node (ref "C33") (pin "1") (pinfunction "1_1") (pintype "passive"))
      (node (ref "C34") (pin "1") (pinfunction "1_1") (pintype "passive"))
      (node (ref "C35") (pin "1") (pinfunction "1_1") (pintype "passive"))
      (node (ref "C36") (pin "1") (pinfunction "1_1") (pintype "passive"))
      (node (ref "C37") (pin "1") (pinfunction "1_1") (pintype "passive"))
      (node (ref "C38") (pin "1") (pinfunction "1_1") (pintype "passive"))
      (node (ref "C39") (pin "1") (pinfunction "1_1") (pintype "passive"))
      (node (ref "C4") (pin "1") (pinfunction "1_1") (pintype "passive"))
      (node (ref "C40") (pin "-") (pinfunction "-_-") (pintype "passive"))
      (node (ref "C41") (pin "1") (pinfunction "1_1") (pintype "passive"))
      (node (ref "C42") (pin "1") (pinfunction "1_1") (pintype "passive"))
      (node (ref "C43") (pin "1") (pinfunction "1_1") (pintype "passive"))
      (node (ref "C44") (pin "1") (pinfunction "1_1") (pintype "passive"))
      (node (ref "C5") (pin "1") (pinfunction "1_1") (pintype "passive"))
      (node (ref "C6") (pin "1") (pinfunction "1_1") (pintype "passive"))
      (node (ref "C7") (pin "1") (pinfunction "1_1") (pintype "passive"))
      (node (ref "C8") (pin "1") (pinfunction "1_1") (pintype "passive"))
      (node (ref "C9") (pin "1") (pinfunction "1_1") (pintype "passive"))
      (node (ref "DA1") (pin "1") (pinfunction "ADJ/GND_1") (pintype "passive"))
      (node (ref "DA2") (pin "1") (pinfunction "ADJ/GND_1") (pintype "passive"))
      (node (ref "DA3") (pin "1") (pinfunction "ADJ/GND_1") (pintype "passive"))
      (node (ref "DD1") (pin "108") (pinfunction "GND_A_108") (pintype "passive"))
      (node (ref "DD1") (pin "118") (pinfunction "GND_118") (pintype "passive"))
      (node (ref "DD1") (pin "123") (pinfunction "GND_123") (pintype "passive"))
      (node (ref "DD1") (pin "131") (pinfunction "GND_131") (pintype "passive"))
      (node (ref "DD1") (pin "140") (pinfunction "GND_140") (pintype "passive"))
      (node (ref "DD1") (pin "145") (pinfunction "GND_145") (pintype "passive"))
      (node (ref "DD1") (pin "19") (pinfunction "GND_19") (pintype "passive"))
      (node (ref "DD1") (pin "21") (pinfunction "nCE_21") (pintype "passive"))
      (node (ref "DD1") (pin "25") (pinfunction "n_CK_25") (pintype "passive"))
      (node (ref "DD1") (pin "27") (pinfunction "GND_27") (pintype "passive"))
      (node (ref "DD1") (pin "36") (pinfunction "GND_A_36") (pintype "passive"))
      (node (ref "DD1") (pin "41") (pinfunction "GND_41") (pintype "passive"))
      (node (ref "DD1") (pin "48") (pinfunction "GND_48") (pintype "passive"))
      (node (ref "DD1") (pin "57") (pinfunction "GND_57") (pintype "passive"))
      (node (ref "DD1") (pin "63") (pinfunction "GND_63") (pintype "passive"))
      (node (ref "DD1") (pin "82") (pinfunction "GND_82") (pintype "passive"))
      (node (ref "DD1") (pin "94") (pinfunction "MSEL0_94") (pintype "passive"))
      (node (ref "DD1") (pin "95") (pinfunction "GND_95") (pintype "passive"))
      (node (ref "DD1") (pin "97") (pinfunction "MSEL2_97") (pintype "passive"))
      (node (ref "DD2") (pin "2") (pinfunction "GND_2") (pintype "passive"))
      (node (ref "DD3") (pin "4") (pinfunction "GND_4") (pintype "passive"))
      (node (ref "R7") (pin "2") (pinfunction "2_2") (pintype "passive"))
      (node (ref "XP1") (pin "10") (pinfunction "10_10") (pintype "passive"))
      (node (ref "XP1") (pin "2") (pinfunction "2_2") (pintype "passive"))
    )
    (net (code "50") (name "Net-(C10-Pad2)") (class "Default")
      (node (ref "C10") (pin "2") (pinfunction "2_2") (pintype "passive"))
      (node (ref "C11") (pin "+") (pinfunction "+_+") (pintype "passive"))
      (node (ref "DA2") (pin "2") (pinfunction "VOUT_2") (pintype "passive"))
      (node (ref "DA2") (pin "4") (pinfunction "VOUT_4") (pintype "passive"))
      (node (ref "L6") (pin "1") (pinfunction "1_1") (pintype "passive"))
    )
    (net (code "51") (name "Net-(C25-Pad2)") (class "Default")
      (node (ref "C25") (pin "2") (pinfunction "2_2") (pintype "passive"))
      (node (ref "C26") (pin "+") (pinfunction "+_+") (pintype "passive"))
      (node (ref "DA1") (pin "2") (pinfunction "VOUT_2") (pintype "passive"))
      (node (ref "DA1") (pin "4") (pinfunction "VOUT_4") (pintype "passive"))
      (node (ref "L2") (pin "1") (pinfunction "1_1") (pintype "passive"))
    )
    (net (code "52") (name "Net-(C27-Pad2)") (class "Default")
      (node (ref "C27") (pin "2") (pinfunction "2_2") (pintype "passive"))
      (node (ref "C28") (pin "+") (pinfunction "+_+") (pintype "passive"))
      (node (ref "DA3") (pin "2") (pinfunction "VOUT_2") (pintype "passive"))
      (node (ref "DA3") (pin "4") (pinfunction "VOUT_4") (pintype "passive"))
      (node (ref "L7") (pin "1") (pinfunction "1_1") (pintype "passive"))
    )
    (net (code "53") (name "Net-(DD1B-I{slash}O-Pad120)") (class "Default")
      (node (ref "DD1") (pin "120") (pinfunction "I/O_120") (pintype "passive"))
      (node (ref "TP1") (pin "1") (pinfunction "1_1") (pintype "passive"))
    )
    (net (code "54") (name "Net-(DD1B-I{slash}O-Pad121)") (class "Default")
      (node (ref "DD1") (pin "121") (pinfunction "I/O_121") (pintype "passive"))
      (node (ref "TP2") (pin "1") (pinfunction "1_1") (pintype "passive"))
    )
    (net (code "55") (name "Net-(DD1B-I{slash}O-Pad124)") (class "Default")
      (node (ref "DD1") (pin "124") (pinfunction "I/O_124") (pintype "passive"))
      (node (ref "TP3") (pin "1") (pinfunction "1_1") (pintype "passive"))
    )
    (net (code "56") (name "Net-(DD1C-I{slash}O-Pad31)") (class "Default")
      (node (ref "DD1") (pin "31") (pinfunction "I/O_31") (pintype "passive"))
      (node (ref "TP5") (pin "1") (pinfunction "1_1") (pintype "passive"))
    )
    (net (code "57") (name "Net-(DD1C-I{slash}O-Pad32)") (class "Default")
      (node (ref "DD1") (pin "32") (pinfunction "I/O_32") (pintype "passive"))
      (node (ref "TP4") (pin "1") (pinfunction "1_1") (pintype "passive"))
    )
    (net (code "58") (name "Net-(DD1C-I{slash}O-Pad34)") (class "Default")
      (node (ref "DD1") (pin "34") (pinfunction "I/O_34") (pintype "passive"))
      (node (ref "TP6") (pin "1") (pinfunction "1_1") (pintype "passive"))
    )
    (net (code "59") (name "Net-(DD2-OUT)") (class "Default")
      (node (ref "DD2") (pin "3") (pinfunction "OUT_3") (pintype "passive"))
      (node (ref "R2") (pin "1") (pinfunction "1_1") (pintype "passive"))
    )
    (net (code "60") (name "Net-(DD2-VDC)") (class "Default")
      (node (ref "C1") (pin "2") (pinfunction "2_2") (pintype "passive"))
      (node (ref "C2") (pin "+") (pinfunction "+_+") (pintype "passive"))
      (node (ref "DD2") (pin "4") (pinfunction "VDC_4") (pintype "passive"))
      (node (ref "L8") (pin "2") (pinfunction "2_2") (pintype "passive"))
    )
    (net (code "61") (name "VCCA1") (class "Default")
      (node (ref "C6") (pin "2") (pinfunction "2_2") (pintype "passive"))
      (node (ref "DD1") (pin "35") (pinfunction "VCA_35") (pintype "passive"))
      (node (ref "L1") (pin "2") (pinfunction "2_2") (pintype "passive"))
    )
    (net (code "62") (name "VCCA2") (class "Default")
      (node (ref "C7") (pin "2") (pinfunction "2_2") (pintype "passive"))
      (node (ref "DD1") (pin "107") (pinfunction "VCA_107") (pintype "passive"))
      (node (ref "L3") (pin "2") (pinfunction "2_2") (pintype "passive"))
    )
    (net (code "63") (name "VCCIO") (class "Default")
      (node (ref "C17") (pin "2") (pinfunction "2_2") (pintype "passive"))
      (node (ref "C18") (pin "2") (pinfunction "2_2") (pintype "passive"))
      (node (ref "C19") (pin "2") (pinfunction "2_2") (pintype "passive"))
      (node (ref "C20") (pin "2") (pinfunction "2_2") (pintype "passive"))
      (node (ref "C21") (pin "2") (pinfunction "2_2") (pintype "passive"))
      (node (ref "C22") (pin "2") (pinfunction "2_2") (pintype "passive"))
      (node (ref "C23") (pin "2") (pinfunction "2_2") (pintype "passive"))
      (node (ref "C24") (pin "2") (pinfunction "2_2") (pintype "passive"))
      (node (ref "C39") (pin "2") (pinfunction "2_2") (pintype "passive"))
      (node (ref "C4") (pin "2") (pinfunction "2_2") (pintype "passive"))
      (node (ref "C40") (pin "+") (pinfunction "+_+") (pintype "passive"))
      (node (ref "C41") (pin "2") (pinfunction "2_2") (pintype "passive"))
      (node (ref "C42") (pin "2") (pinfunction "2_2") (pintype "passive"))
      (node (ref "C43") (pin "2") (pinfunction "2_2") (pintype "passive"))
      (node (ref "C44") (pin "2") (pinfunction "2_2") (pintype "passive"))
      (node (ref "C5") (pin "2") (pinfunction "2_2") (pintype "passive"))
      (node (ref "DD1") (pin "117") (pinfunction "VCCIO_117") (pintype "passive"))
      (node (ref "DD1") (pin "122") (pinfunction "VCCIO_122") (pintype "passive"))
      (node (ref "DD1") (pin "130") (pinfunction "VCCIO_130") (pintype "passive"))
      (node (ref "DD1") (pin "139") (pinfunction "VCCIO_139") (pintype "passive"))
      (node (ref "DD1") (pin "17") (pinfunction "VCCIO_17") (pintype "passive"))
      (node (ref "DD1") (pin "26") (pinfunction "VCCIO_26") (pintype "passive"))
      (node (ref "DD1") (pin "40") (pinfunction "VCCIO_40") (pintype "passive"))
      (node (ref "DD1") (pin "47") (pinfunction "VCCIO_47") (pintype "passive"))
      (node (ref "DD1") (pin "56") (pinfunction "VCCIO_56") (pintype "passive"))
      (node (ref "DD1") (pin "62") (pinfunction "VCCIO_62") (pintype "passive"))
      (node (ref "DD1") (pin "81") (pinfunction "VCCIO_81") (pintype "passive"))
      (node (ref "DD1") (pin "93") (pinfunction "VCCIO_93") (pintype "passive"))
      (node (ref "DD1") (pin "96") (pinfunction "MSEL1_96") (pintype "passive"))
      (node (ref "DD3") (pin "3") (pinfunction "VCC_3") (pintype "passive"))
      (node (ref "DD3") (pin "7") (pinfunction "VCC_7") (pintype "passive"))
      (node (ref "DD3") (pin "8") (pinfunction "VCC_8") (pintype "passive"))
      (node (ref "L2") (pin "2") (pinfunction "2_2") (pintype "passive"))
      (node (ref "L8") (pin "1") (pinfunction "1_1") (pintype "passive"))
      (node (ref "R3") (pin "2") (pinfunction "2_2") (pintype "passive"))
      (node (ref "R4") (pin "2") (pinfunction "2_2") (pintype "passive"))
      (node (ref "R5") (pin "2") (pinfunction "2_2") (pintype "passive"))
      (node (ref "R6") (pin "2") (pinfunction "2_2") (pintype "passive"))
      (node (ref "R8") (pin "2") (pinfunction "2_2") (pintype "passive"))
      (node (ref "R9") (pin "2") (pinfunction "2_2") (pintype "passive"))
      (node (ref "XP1") (pin "4") (pinfunction "4_4") (pintype "passive"))
    )
    (net (code "64") (name "VCC_PL1") (class "Default")
      (node (ref "C8") (pin "2") (pinfunction "2_2") (pintype "passive"))
      (node (ref "DD1") (pin "37") (pinfunction "VC_PLL_37") (pintype "passive"))
      (node (ref "L4") (pin "2") (pinfunction "2_2") (pintype "passive"))
    )
    (net (code "65") (name "VCC_PL2") (class "Default")
      (node (ref "C9") (pin "2") (pinfunction "2_2") (pintype "passive"))
      (node (ref "DD1") (pin "109") (pinfunction "VC_PLL_109") (pintype "passive"))
      (node (ref "L5") (pin "2") (pinfunction "2_2") (pintype "passive"))
    )
    (net (code "66") (name "VCINT") (class "Default")
      (node (ref "C29") (pin "2") (pinfunction "2_2") (pintype "passive"))
      (node (ref "C30") (pin "+") (pinfunction "+_+") (pintype "passive"))
      (node (ref "C31") (pin "2") (pinfunction "2_2") (pintype "passive"))
      (node (ref "C32") (pin "2") (pinfunction "2_2") (pintype "passive"))
      (node (ref "C33") (pin "2") (pinfunction "2_2") (pintype "passive"))
      (node (ref "C34") (pin "2") (pinfunction "2_2") (pintype "passive"))
      (node (ref "C35") (pin "2") (pinfunction "2_2") (pintype "passive"))
      (node (ref "C36") (pin "2") (pinfunction "2_2") (pintype "passive"))
      (node (ref "C37") (pin "2") (pinfunction "2_2") (pintype "passive"))
      (node (ref "C38") (pin "2") (pinfunction "2_2") (pintype "passive"))
      (node (ref "DD1") (pin "102") (pinfunction "VCINT_102") (pintype "passive"))
      (node (ref "DD1") (pin "116") (pinfunction "VCINT_116") (pintype "passive"))
      (node (ref "DD1") (pin "134") (pinfunction "VCINT_134") (pintype "passive"))
      (node (ref "DD1") (pin "29") (pinfunction "VCINT_29") (pintype "passive"))
      (node (ref "DD1") (pin "45") (pinfunction "VCINT_45") (pintype "passive"))
      (node (ref "DD1") (pin "5") (pinfunction "VCINT_5") (pintype "passive"))
      (node (ref "DD1") (pin "61") (pinfunction "VCINT_61") (pintype "passive"))
      (node (ref "DD1") (pin "78") (pinfunction "VCINT_78") (pintype "passive"))
      (node (ref "L4") (pin "1") (pinfunction "1_1") (pintype "passive"))
      (node (ref "L5") (pin "1") (pinfunction "1_1") (pintype "passive"))
      (node (ref "L7") (pin "2") (pinfunction "2_2") (pintype "passive"))
    )
    (net (code "67") (name "unconnected-(DD1C-CLK0-Pad22)") (class "Default")
      (node (ref "DD1") (pin "22") (pinfunction "CLK0_22") (pintype "passive"))
    )
    (net (code "68") (name "unconnected-(DD1C-CLK1-Pad23)") (class "Default")
      (node (ref "DD1") (pin "23") (pinfunction "CLK1_23") (pintype "passive"))
    )
    (net (code "69") (name "unconnected-(DD1C-CLK4-Pad91)") (class "Default")
      (node (ref "DD1") (pin "91") (pinfunction "CLK4_91") (pintype "passive"))
    )
    (net (code "70") (name "unconnected-(DD1C-CLK5-Pad90)") (class "Default")
      (node (ref "DD1") (pin "90") (pinfunction "CLK5_90") (pintype "passive"))
    )
    (net (code "71") (name "unconnected-(DD1C-CLK6-Pad89)") (class "Default")
      (node (ref "DD1") (pin "89") (pinfunction "CLK6_89") (pintype "passive"))
    )
    (net (code "72") (name "unconnected-(DD1C-CLK7-Pad88)") (class "Default")
      (node (ref "DD1") (pin "88") (pinfunction "CLK7_88") (pintype "passive"))
    )
    (net (code "73") (name "unconnected-(DD1C-I{slash}O-Pad1)") (class "Default")
      (node (ref "DD1") (pin "1") (pinfunction "I/O_1") (pintype "passive"))
    )
    (net (code "74") (name "unconnected-(DD1C-I{slash}O-Pad2)") (class "Default")
      (node (ref "DD1") (pin "2") (pinfunction "I/O_2") (pintype "passive"))
    )
    (net (code "75") (name "unconnected-(DD1C-I{slash}O-Pad3)") (class "Default")
      (node (ref "DD1") (pin "3") (pinfunction "I/O_3") (pintype "passive"))
    )
    (net (code "76") (name "unconnected-(DD1C-I{slash}O-Pad4)") (class "Default")
      (node (ref "DD1") (pin "4") (pinfunction "I/O_4") (pintype "passive"))
    )
    (net (code "77") (name "unconnected-(DD1C-I{slash}O-Pad7)") (class "Default")
      (node (ref "DD1") (pin "7") (pinfunction "I/O_7") (pintype "passive"))
    )
    (net (code "78") (name "unconnected-(DD1C-I{slash}O-Pad10)") (class "Default")
      (node (ref "DD1") (pin "10") (pinfunction "I/O_10") (pintype "passive"))
    )
    (net (code "79") (name "unconnected-(DD1C-I{slash}O-Pad11)") (class "Default")
      (node (ref "DD1") (pin "11") (pinfunction "I/O_11") (pintype "passive"))
    )
    (net (code "80") (name "unconnected-(DD1C-I{slash}O-Pad28)") (class "Default")
      (node (ref "DD1") (pin "28") (pinfunction "I/O_28") (pintype "passive"))
    )
    (net (code "81") (name "unconnected-(DD1C-I{slash}O-Pad30)") (class "Default")
      (node (ref "DD1") (pin "30") (pinfunction "I/O_30") (pintype "passive"))
    )
    (net (code "82") (name "unconnected-(DD1C-I{slash}O-Pad33)") (class "Default")
      (node (ref "DD1") (pin "33") (pinfunction "I/O_33") (pintype "passive"))
    )
    (net (code "83") (name "unconnected-(DD1C-I{slash}O-Pad38)") (class "Default")
      (node (ref "DD1") (pin "38") (pinfunction "I/O_38") (pintype "passive"))
    )
    (net (code "84") (name "unconnected-(DD1C-I{slash}O-Pad39)") (class "Default")
      (node (ref "DD1") (pin "39") (pinfunction "I/O_39") (pintype "passive"))
    )
    (net (code "85") (name "unconnected-(DD1C-I{slash}O-Pad42)") (class "Default")
      (node (ref "DD1") (pin "42") (pinfunction "I/O_42") (pintype "passive"))
    )
    (net (code "86") (name "unconnected-(DD1C-I{slash}O-Pad43)") (class "Default")
      (node (ref "DD1") (pin "43") (pinfunction "I/O_43") (pintype "passive"))
    )
    (net (code "87") (name "unconnected-(DD1C-I{slash}O-Pad44)") (class "Default")
      (node (ref "DD1") (pin "44") (pinfunction "I/O_44") (pintype "passive"))
    )
    (net (code "88") (name "unconnected-(DD1C-I{slash}O-Pad46)") (class "Default")
      (node (ref "DD1") (pin "46") (pinfunction "I/O_46") (pintype "passive"))
    )
    (net (code "89") (name "unconnected-(DD1C-I{slash}O-Pad50)") (class "Default")
      (node (ref "DD1") (pin "50") (pinfunction "I/O_50") (pintype "passive"))
    )
    (net (code "90") (name "unconnected-(DD1C-I{slash}O-Pad51)") (class "Default")
      (node (ref "DD1") (pin "51") (pinfunction "I/O_51") (pintype "passive"))
    )
    (net (code "91") (name "unconnected-(DD1C-I{slash}O-Pad52)") (class "Default")
      (node (ref "DD1") (pin "52") (pinfunction "I/O_52") (pintype "passive"))
    )
    (net (code "92") (name "unconnected-(DD1C-I{slash}O-Pad54)") (class "Default")
      (node (ref "DD1") (pin "54") (pinfunction "I/O_54") (pintype "passive"))
    )
    (net (code "93") (name "unconnected-(DD1C-I{slash}O-Pad55)") (class "Default")
      (node (ref "DD1") (pin "55") (pinfunction "I/O_55") (pintype "passive"))
    )
    (net (code "94") (name "unconnected-(DD1C-I{slash}O-Pad64)") (class "Default")
      (node (ref "DD1") (pin "64") (pinfunction "I/O_64") (pintype "passive"))
    )
    (net (code "95") (name "unconnected-(DD1C-I{slash}O-Pad65)") (class "Default")
      (node (ref "DD1") (pin "65") (pinfunction "I/O_65") (pintype "passive"))
    )
    (net (code "96") (name "unconnected-(DD1C-I{slash}O-Pad66)") (class "Default")
      (node (ref "DD1") (pin "66") (pinfunction "I/O_66") (pintype "passive"))
    )
    (net (code "97") (name "unconnected-(DD1C-I{slash}O-Pad67)") (class "Default")
      (node (ref "DD1") (pin "67") (pinfunction "I/O_67") (pintype "passive"))
    )
    (net (code "98") (name "unconnected-(DD1C-I{slash}O-Pad68)") (class "Default")
      (node (ref "DD1") (pin "68") (pinfunction "I/O_68") (pintype "passive"))
    )
    (net (code "99") (name "unconnected-(DD1C-I{slash}O-Pad79)") (class "Default")
      (node (ref "DD1") (pin "79") (pinfunction "I/O_79") (pintype "passive"))
    )
    (net (code "100") (name "unconnected-(DD1C-I{slash}O-Pad86)") (class "Default")
      (node (ref "DD1") (pin "86") (pinfunction "I/O_86") (pintype "passive"))
    )
    (net (code "101") (name "unconnected-(DD1C-I{slash}O-Pad87)") (class "Default")
      (node (ref "DD1") (pin "87") (pinfunction "I/O_87") (pintype "passive"))
    )
    (net (code "102") (name "unconnected-(DD1C-I{slash}O-Pad100)") (class "Default")
      (node (ref "DD1") (pin "100") (pinfunction "I/O_100") (pintype "passive"))
    )
    (net (code "103") (name "unconnected-(DD1C-I{slash}O-Pad101)") (class "Default")
      (node (ref "DD1") (pin "101") (pinfunction "I/O_101") (pintype "passive"))
    )
    (net (code "104") (name "unconnected-(DD1C-I{slash}O-Pad103)") (class "Default")
      (node (ref "DD1") (pin "103") (pinfunction "I/O_103") (pintype "passive"))
    )
    (net (code "105") (name "unconnected-(DD1C-I{slash}O-Pad105)") (class "Default")
      (node (ref "DD1") (pin "105") (pinfunction "I/O_105") (pintype "passive"))
    )
    (net (code "106") (name "unconnected-(DD1C-I{slash}O-Pad106)") (class "Default")
      (node (ref "DD1") (pin "106") (pinfunction "I/O_106") (pintype "passive"))
    )
    (net (code "107") (name "unconnected-(DD1C-I{slash}O-Pad113)") (class "Default")
      (node (ref "DD1") (pin "113") (pinfunction "I/O_113") (pintype "passive"))
    )
    (net (code "108") (name "unconnected-(DD1C-I{slash}O-Pad114)") (class "Default")
      (node (ref "DD1") (pin "114") (pinfunction "I/O_114") (pintype "passive"))
    )
    (net (code "109") (name "unconnected-(DD1C-I{slash}O-Pad128)") (class "Default")
      (node (ref "DD1") (pin "128") (pinfunction "I/O_128") (pintype "passive"))
    )
    (net (code "110") (name "unconnected-(DD1C-I{slash}O-Pad129)") (class "Default")
      (node (ref "DD1") (pin "129") (pinfunction "I/O_129") (pintype "passive"))
    )
    (net (code "111") (name "unconnected-(DD1C-I{slash}O-Pad135)") (class "Default")
      (node (ref "DD1") (pin "135") (pinfunction "I/O_135") (pintype "passive"))
    )
    (net (code "112") (name "unconnected-(DD1C-I{slash}O-Pad141)") (class "Default")
      (node (ref "DD1") (pin "141") (pinfunction "I/O_141") (pintype "passive"))
    )
    (net (code "113") (name "unconnected-(DD1C-I{slash}O-Pad142)") (class "Default")
      (node (ref "DD1") (pin "142") (pinfunction "I/O_142") (pintype "passive"))
    )
    (net (code "114") (name "unconnected-(DD1C-I{slash}O-Pad143)") (class "Default")
      (node (ref "DD1") (pin "143") (pinfunction "I/O_143") (pintype "passive"))
    )
    (net (code "115") (name "unconnected-(DD1C-I{slash}O-Pad144)") (class "Default")
      (node (ref "DD1") (pin "144") (pinfunction "I/O_144") (pintype "passive"))
    )
    (net (code "116") (name "unconnected-(DD2-E{slash}D-Pad1)") (class "Default")
      (node (ref "DD2") (pin "1") (pinfunction "E/D_1") (pintype "passive+no_connect"))
    )
    (net (code "117") (name "unconnected-(XP1-Pad6)") (class "Default")
      (node (ref "XP1") (pin "6") (pinfunction "6_6") (pintype "passive+no_connect"))
    )
    (net (code "118") (name "unconnected-(XP1-Pad7)") (class "Default")
      (node (ref "XP1") (pin "7") (pinfunction "7_7") (pintype "passive+no_connect"))
    )
    (net (code "119") (name "unconnected-(XP1-Pad8)") (class "Default")
      (node (ref "XP1") (pin "8") (pinfunction "8_8") (pintype "passive+no_connect"))
    )
  )
)
